# full.net
KiCad netlist of a schematic drawn in EAGLE
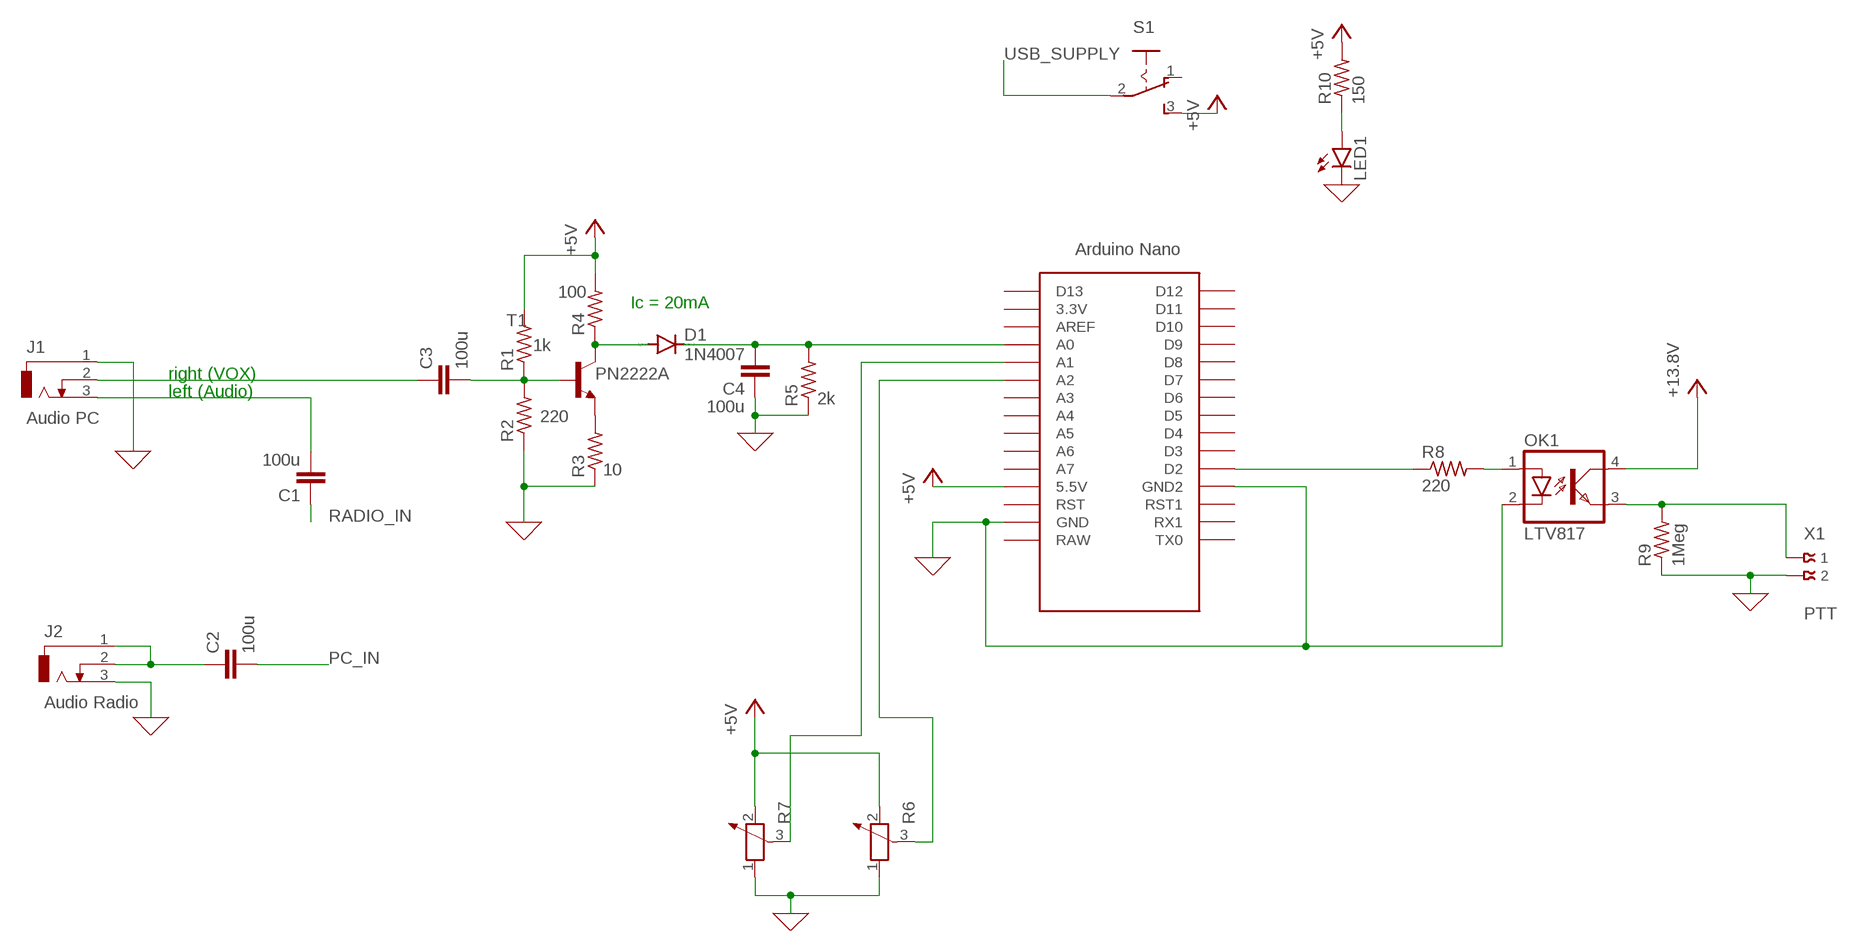
[diagram p0: schematic, sheet 1]

(export (version "E")
  (design (tool "Eeschema 10.0.6"))
  (components
    (comp (ref "C1")
      (value "100u")
      (footprint "eagle-import:C025-024X044")
      (libsource (lib "eagle-import") (part "C-EU025-024X044"))
    )
    (comp (ref "C2")
      (value "100u")
      (footprint "eagle-import:C025-024X044")
      (libsource (lib "eagle-import") (part "C-EU025-024X044"))
    )
    (comp (ref "C3")
      (value "100u")
      (footprint "eagle-import:C025-024X044")
      (libsource (lib "eagle-import") (part "C-EU025-024X044"))
    )
    (comp (ref "C4")
      (value "100u")
      (footprint "eagle-import:C025-024X044")
      (libsource (lib "eagle-import") (part "C-EU025-024X044"))
    )
    (comp (ref "D1")
      (value "1N4007")
      (footprint "eagle-import:DO41-10")
      (libsource (lib "eagle-import") (part "1N4004"))
    )
    (comp (ref "J1")
      (value "Audio PC")
      (footprint "eagle-import:DCJ0202")
      (libsource (lib "eagle-import") (part "DCJ0202"))
    )
    (comp (ref "J2")
      (value "Audio Radio")
      (footprint "eagle-import:DCJ0202")
      (libsource (lib "eagle-import") (part "DCJ0202"))
    )
    (comp (ref "LED1")
      (value "LAP4-TOP")
      (footprint "eagle-import:P47F-TOP")
      (libsource (lib "eagle-import") (part "P4-TOPLA"))
    )
    (comp (ref "OK1")
      (value "LTV817")
      (footprint "eagle-import:DIP4")
      (fields (field (name "MF") "VISHAY/TELEFUNKEN") (field (name "MPN") "SFH618A-2"))
      (libsource (lib "eagle-import") (part "SFH618?A-2"))
    )
    (comp (ref "R1")
      (value "1k")
      (footprint "eagle-import:0204V")
      (libsource (lib "eagle-import") (part "R-US_0204/2V"))
    )
    (comp (ref "R2")
      (value "220")
      (footprint "eagle-import:0204V")
      (libsource (lib "eagle-import") (part "R-US_0204/2V"))
    )
    (comp (ref "R3")
      (value "10")
      (footprint "eagle-import:0204V")
      (libsource (lib "eagle-import") (part "R-US_0204/2V"))
    )
    (comp (ref "R4")
      (value "100")
      (footprint "eagle-import:0204V")
      (libsource (lib "eagle-import") (part "R-US_0204/2V"))
    )
    (comp (ref "R5")
      (value "2k")
      (footprint "eagle-import:0204V")
      (libsource (lib "eagle-import") (part "R-US_0204/2V"))
    )
    (comp (ref "R6")
      (value "POTENTIOMETER_PT-10S")
      (footprint "eagle-import:PT-10S")
      (libsource (lib "eagle-import") (part "POTENTIOMETER_PT-10S"))
    )
    (comp (ref "R7")
      (value "POTENTIOMETER_PT-10S")
      (footprint "eagle-import:PT-10S")
      (libsource (lib "eagle-import") (part "POTENTIOMETER_PT-10S"))
    )
    (comp (ref "R8")
      (value "220")
      (footprint "eagle-import:0204V")
      (libsource (lib "eagle-import") (part "R-US_0204/2V"))
    )
    (comp (ref "R9")
      (value "1Meg")
      (footprint "eagle-import:0204V")
      (libsource (lib "eagle-import") (part "R-US_0204/2V"))
    )
    (comp (ref "R10")
      (value "150")
      (footprint "eagle-import:0204V")
      (libsource (lib "eagle-import") (part "R-US_0204/2V"))
    )
    (comp (ref "S1")
      (value "255SB")
      (footprint "eagle-import:255SB")
      (libsource (lib "eagle-import") (part "255SB"))
    )
    (comp (ref "T1")
      (value "PN2222A")
      (footprint "eagle-import:TO5")
      (libsource (lib "eagle-import") (part "2N3440"))
    )
    (comp (ref "U$1")
      (value "NANO")
      (footprint "eagle-import:NANO")
      (libsource (lib "eagle-import") (part "NANO"))
    )
    (comp (ref "X1")
      (value "PTT")
      (footprint "eagle-import:009176002")
      (fields (field (name "MPN") "009176002001006"))
      (libsource (lib "eagle-import") (part "00917?0026"))
    )
  )
  (nets
    (net (code "1") (name "+5V") (class "Default")
      (node (ref "R1") (pin "2") (pinfunction "2_2") (pintype "passive"))
      (node (ref "R10") (pin "2") (pinfunction "2_2") (pintype "passive"))
      (node (ref "R4") (pin "2") (pinfunction "2_2") (pintype "passive"))
      (node (ref "R6") (pin "2") (pinfunction "2_2") (pintype "passive"))
      (node (ref "R7") (pin "2") (pinfunction "2_2") (pintype "passive"))
      (node (ref "S1") (pin "3") (pinfunction "S_3") (pintype "passive"))
      (node (ref "U$1") (pin "5V") (pinfunction "5.5V_5V") (pintype "bidirectional"))
    )
    (net (code "2") (name "+13.8V") (class "Default")
      (node (ref "OK1") (pin "4") (pinfunction "COL_4") (pintype "passive"))
    )
    (net (code "3") (name "/PC_IN") (class "Default")
      (node (ref "C2") (pin "2") (pinfunction "2_2") (pintype "passive"))
    )
    (net (code "4") (name "/RADIO_IN") (class "Default")
      (node (ref "C1") (pin "1") (pinfunction "1_1") (pintype "passive"))
    )
    (net (code "5") (name "/USB_SUPPLY") (class "Default")
      (node (ref "S1") (pin "2") (pinfunction "P_2") (pintype "passive"))
    )
    (net (code "6") (name "GND") (class "Default")
      (node (ref "C4") (pin "1") (pinfunction "1_1") (pintype "passive"))
      (node (ref "J1") (pin "1") (pinfunction "1_1") (pintype "passive"))
      (node (ref "J2") (pin "3") (pinfunction "3_3") (pintype "passive"))
      (node (ref "LED1") (pin "C") (pinfunction "C_C") (pintype "passive"))
      (node (ref "OK1") (pin "2") (pinfunction "C_2") (pintype "passive"))
      (node (ref "R2") (pin "1") (pinfunction "1_1") (pintype "passive"))
      (node (ref "R3") (pin "1") (pinfunction "1_1") (pintype "passive"))
      (node (ref "R5") (pin "1") (pinfunction "1_1") (pintype "passive"))
      (node (ref "R6") (pin "1") (pinfunction "1_1") (pintype "passive"))
      (node (ref "R7") (pin "1") (pinfunction "1_1") (pintype "passive"))
      (node (ref "R9") (pin "1") (pinfunction "1_1") (pintype "passive"))
      (node (ref "U$1") (pin "GND") (pinfunction "GND_GND") (pintype "bidirectional"))
      (node (ref "U$1") (pin "GND1") (pinfunction "GND2_GND1") (pintype "bidirectional"))
      (node (ref "X1") (pin "2") (pinfunction "2_2") (pintype "passive"))
    )
    (net (code "7") (name "Net-(C1-Pad2)") (class "Default")
      (node (ref "C1") (pin "2") (pinfunction "2_2") (pintype "passive"))
      (node (ref "J1") (pin "3") (pinfunction "3_3") (pintype "passive"))
    )
    (net (code "8") (name "Net-(C2-Pad1)") (class "Default")
      (node (ref "C2") (pin "1") (pinfunction "1_1") (pintype "passive"))
      (node (ref "J2") (pin "1") (pinfunction "1_1") (pintype "passive"))
      (node (ref "J2") (pin "2") (pinfunction "2_2") (pintype "passive"))
    )
    (net (code "9") (name "Net-(C3-Pad1)") (class "Default")
      (node (ref "C3") (pin "1") (pinfunction "1_1") (pintype "passive"))
      (node (ref "J1") (pin "2") (pinfunction "2_2") (pintype "passive"))
    )
    (net (code "10") (name "Net-(C4-Pad2)") (class "Default")
      (node (ref "C4") (pin "2") (pinfunction "2_2") (pintype "passive"))
      (node (ref "D1") (pin "C") (pinfunction "C_C") (pintype "passive"))
      (node (ref "R5") (pin "2") (pinfunction "2_2") (pintype "passive"))
      (node (ref "U$1") (pin "A0") (pinfunction "A0_A0") (pintype "bidirectional"))
    )
    (net (code "11") (name "Net-(LED1-PadA)") (class "Default")
      (node (ref "LED1") (pin "A") (pinfunction "A_A") (pintype "passive"))
      (node (ref "R10") (pin "1") (pinfunction "1_1") (pintype "passive"))
    )
    (net (code "12") (name "Net-(OK1-A)") (class "Default")
      (node (ref "OK1") (pin "1") (pinfunction "A_1") (pintype "passive"))
      (node (ref "R8") (pin "2") (pinfunction "2_2") (pintype "passive"))
    )
    (net (code "13") (name "Net-(OK1-EMIT)") (class "Default")
      (node (ref "OK1") (pin "3") (pinfunction "EMIT_3") (pintype "passive"))
      (node (ref "R9") (pin "2") (pinfunction "2_2") (pintype "passive"))
      (node (ref "X1") (pin "1") (pinfunction "1_1") (pintype "passive"))
    )
    (net (code "14") (name "Net-(R6-Pad3)") (class "Default")
      (node (ref "R6") (pin "3") (pinfunction "3_3") (pintype "passive"))
      (node (ref "U$1") (pin "A2") (pinfunction "A2_A2") (pintype "bidirectional"))
    )
    (net (code "15") (name "Net-(R7-Pad3)") (class "Default")
      (node (ref "R7") (pin "3") (pinfunction "3_3") (pintype "passive"))
      (node (ref "U$1") (pin "A1") (pinfunction "A1_A1") (pintype "bidirectional"))
    )
    (net (code "16") (name "Net-(R8-Pad1)") (class "Default")
      (node (ref "R8") (pin "1") (pinfunction "1_1") (pintype "passive"))
      (node (ref "U$1") (pin "D2") (pinfunction "D2_D2") (pintype "bidirectional"))
    )
    (net (code "17") (name "Net-(T1-B)") (class "Default")
      (node (ref "C3") (pin "2") (pinfunction "2_2") (pintype "passive"))
      (node (ref "R1") (pin "1") (pinfunction "1_1") (pintype "passive"))
      (node (ref "R2") (pin "2") (pinfunction "2_2") (pintype "passive"))
      (node (ref "T1") (pin "2") (pinfunction "B_2") (pintype "passive"))
    )
    (net (code "18") (name "Net-(T1-C)") (class "Default")
      (node (ref "D1") (pin "A") (pinfunction "A_A") (pintype "passive"))
      (node (ref "R4") (pin "1") (pinfunction "1_1") (pintype "passive"))
      (node (ref "T1") (pin "3") (pinfunction "C_3") (pintype "passive"))
    )
    (net (code "19") (name "Net-(T1-E)") (class "Default")
      (node (ref "R3") (pin "2") (pinfunction "2_2") (pintype "passive"))
      (node (ref "T1") (pin "1") (pinfunction "E_1") (pintype "passive"))
    )
    (net (code "20") (name "unconnected-(S1-O-Pad1)") (class "Default")
      (node (ref "S1") (pin "1") (pinfunction "O_1") (pintype "passive"))
    )
    (net (code "21") (name "unconnected-(U$1-Pad3.3V)") (class "Default")
      (node (ref "U$1") (pin "3.3V") (pinfunction "3.3V_3.3V") (pintype "bidirectional"))
    )
    (net (code "22") (name "unconnected-(U$1-PadA3)") (class "Default")
      (node (ref "U$1") (pin "A3") (pinfunction "A3_A3") (pintype "bidirectional"))
    )
    (net (code "23") (name "unconnected-(U$1-PadA4)") (class "Default")
      (node (ref "U$1") (pin "A4") (pinfunction "A4_A4") (pintype "bidirectional"))
    )
    (net (code "24") (name "unconnected-(U$1-PadA5)") (class "Default")
      (node (ref "U$1") (pin "A5") (pinfunction "A5_A5") (pintype "bidirectional"))
    )
    (net (code "25") (name "unconnected-(U$1-PadA6)") (class "Default")
      (node (ref "U$1") (pin "A6") (pinfunction "A6_A6") (pintype "bidirectional"))
    )
    (net (code "26") (name "unconnected-(U$1-PadA7)") (class "Default")
      (node (ref "U$1") (pin "A7") (pinfunction "A7_A7") (pintype "bidirectional"))
    )
    (net (code "27") (name "unconnected-(U$1-PadAREF)") (class "Default")
      (node (ref "U$1") (pin "AREF") (pinfunction "AREF_AREF") (pintype "bidirectional"))
    )
    (net (code "28") (name "unconnected-(U$1-PadD3)") (class "Default")
      (node (ref "U$1") (pin "D3") (pinfunction "D3_D3") (pintype "bidirectional"))
    )
    (net (code "29") (name "unconnected-(U$1-PadD4)") (class "Default")
      (node (ref "U$1") (pin "D4") (pinfunction "D4_D4") (pintype "bidirectional"))
    )
    (net (code "30") (name "unconnected-(U$1-PadD5)") (class "Default")
      (node (ref "U$1") (pin "D5") (pinfunction "D5_D5") (pintype "bidirectional"))
    )
    (net (code "31") (name "unconnected-(U$1-PadD6)") (class "Default")
      (node (ref "U$1") (pin "D6") (pinfunction "D6_D6") (pintype "bidirectional"))
    )
    (net (code "32") (name "unconnected-(U$1-PadD7)") (class "Default")
      (node (ref "U$1") (pin "D7") (pinfunction "D7_D7") (pintype "bidirectional"))
    )
    (net (code "33") (name "unconnected-(U$1-PadD8)") (class "Default")
      (node (ref "U$1") (pin "D8") (pinfunction "D8_D8") (pintype "bidirectional"))
    )
    (net (code "34") (name "unconnected-(U$1-PadD9)") (class "Default")
      (node (ref "U$1") (pin "D9") (pinfunction "D9_D9") (pintype "bidirectional"))
    )
    (net (code "35") (name "unconnected-(U$1-PadD10)") (class "Default")
      (node (ref "U$1") (pin "D10") (pinfunction "D10_D10") (pintype "bidirectional"))
    )
    (net (code "36") (name "unconnected-(U$1-PadD11)") (class "Default")
      (node (ref "U$1") (pin "D11") (pinfunction "D11_D11") (pintype "bidirectional"))
    )
    (net (code "37") (name "unconnected-(U$1-PadD12)") (class "Default")
      (node (ref "U$1") (pin "D12") (pinfunction "D12_D12") (pintype "bidirectional"))
    )
    (net (code "38") (name "unconnected-(U$1-PadD13)") (class "Default")
      (node (ref "U$1") (pin "D13") (pinfunction "D13_D13") (pintype "bidirectional"))
    )
    (net (code "39") (name "unconnected-(U$1-PadICSP1)") (class "Default")
      (node (ref "U$1") (pin "ICSP1") (pinfunction "ICSP1_ICSP1") (pintype "bidirectional"))
    )
    (net (code "40") (name "unconnected-(U$1-PadICSP2)") (class "Default")
      (node (ref "U$1") (pin "ICSP2") (pinfunction "ICSP2_ICSP2") (pintype "bidirectional"))
    )
    (net (code "41") (name "unconnected-(U$1-PadICSP3)") (class "Default")
      (node (ref "U$1") (pin "ICSP3") (pinfunction "ICSP3_ICSP3") (pintype "bidirectional"))
    )
    (net (code "42") (name "unconnected-(U$1-PadICSP4)") (class "Default")
      (node (ref "U$1") (pin "ICSP4") (pinfunction "ICSP4_ICSP4") (pintype "bidirectional"))
    )
    (net (code "43") (name "unconnected-(U$1-PadICSP5)") (class "Default")
      (node (ref "U$1") (pin "ICSP5") (pinfunction "ICSP5_ICSP5") (pintype "bidirectional"))
    )
    (net (code "44") (name "unconnected-(U$1-PadICSP6)") (class "Default")
      (node (ref "U$1") (pin "ICSP6") (pinfunction "ICSP6_ICSP6") (pintype "bidirectional"))
    )
    (net (code "45") (name "unconnected-(U$1-PadRAW)") (class "Default")
      (node (ref "U$1") (pin "RAW") (pinfunction "RAW_RAW") (pintype "bidirectional"))
    )
    (net (code "46") (name "unconnected-(U$1-PadRST)") (class "Default")
      (node (ref "U$1") (pin "RST") (pinfunction "RST_RST") (pintype "bidirectional"))
    )
    (net (code "47") (name "unconnected-(U$1-PadRST1)") (class "Default")
      (node (ref "U$1") (pin "RST1") (pinfunction "RST1_RST1") (pintype "bidirectional"))
    )
    (net (code "48") (name "unconnected-(U$1-PadRX1)") (class "Default")
      (node (ref "U$1") (pin "RX1") (pinfunction "RX1_RX1") (pintype "bidirectional"))
    )
    (net (code "49") (name "unconnected-(U$1-PadTX0)") (class "Default")
      (node (ref "U$1") (pin "TX0") (pinfunction "TX0_TX0") (pintype "bidirectional"))
    )
  )
)
